# PhotoTriac.net
KiCad netlist of a schematic drawn in EAGLE
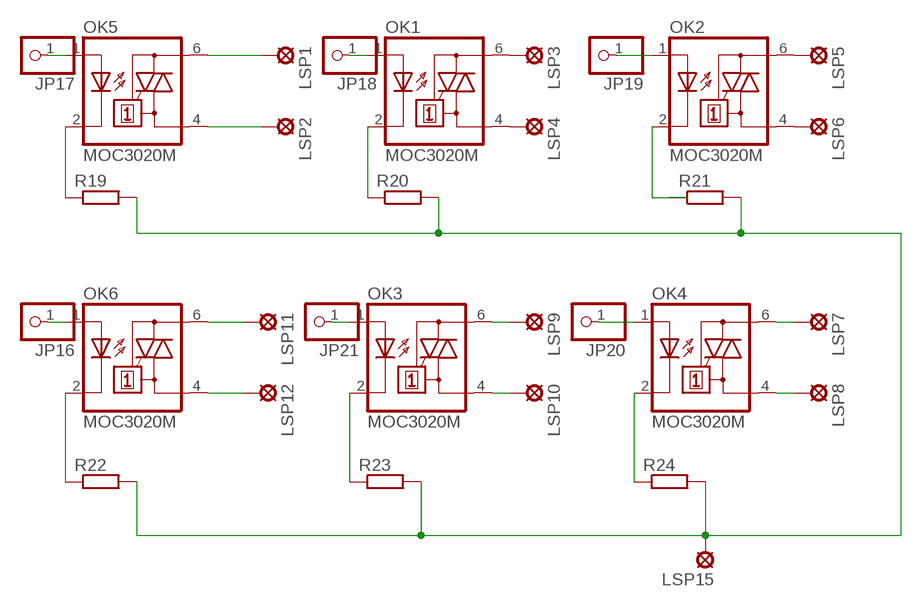
[diagram p0: schematic, sheet 1]

(export (version "E")
  (design (tool "Eeschema 10.0.6"))
  (components
    (comp (ref "JP16")
      (value "PINHD-1X1")
      (footprint "eagle-import:1X01")
      (libsource (lib "eagle-import") (part "PINHD-1X1"))
    )
    (comp (ref "JP17")
      (value "PINHD-1X1")
      (footprint "eagle-import:1X01")
      (libsource (lib "eagle-import") (part "PINHD-1X1"))
    )
    (comp (ref "JP18")
      (value "PINHD-1X1")
      (footprint "eagle-import:1X01")
      (libsource (lib "eagle-import") (part "PINHD-1X1"))
    )
    (comp (ref "JP19")
      (value "PINHD-1X1")
      (footprint "eagle-import:1X01")
      (libsource (lib "eagle-import") (part "PINHD-1X1"))
    )
    (comp (ref "JP20")
      (value "PINHD-1X1")
      (footprint "eagle-import:1X01")
      (libsource (lib "eagle-import") (part "PINHD-1X1"))
    )
    (comp (ref "JP21")
      (value "PINHD-1X1")
      (footprint "eagle-import:1X01")
      (libsource (lib "eagle-import") (part "PINHD-1X1"))
    )
    (comp (ref "LSP1")
      (value "LSP10")
      (footprint "eagle-import:LSP10")
      (libsource (lib "eagle-import") (part "LSP10"))
    )
    (comp (ref "LSP2")
      (value "LSP10")
      (footprint "eagle-import:LSP10")
      (libsource (lib "eagle-import") (part "LSP10"))
    )
    (comp (ref "LSP3")
      (value "LSP10")
      (footprint "eagle-import:LSP10")
      (libsource (lib "eagle-import") (part "LSP10"))
    )
    (comp (ref "LSP4")
      (value "LSP10")
      (footprint "eagle-import:LSP10")
      (libsource (lib "eagle-import") (part "LSP10"))
    )
    (comp (ref "LSP5")
      (value "LSP10")
      (footprint "eagle-import:LSP10")
      (libsource (lib "eagle-import") (part "LSP10"))
    )
    (comp (ref "LSP6")
      (value "LSP10")
      (footprint "eagle-import:LSP10")
      (libsource (lib "eagle-import") (part "LSP10"))
    )
    (comp (ref "LSP7")
      (value "LSP10")
      (footprint "eagle-import:LSP10")
      (libsource (lib "eagle-import") (part "LSP10"))
    )
    (comp (ref "LSP8")
      (value "LSP10")
      (footprint "eagle-import:LSP10")
      (libsource (lib "eagle-import") (part "LSP10"))
    )
    (comp (ref "LSP9")
      (value "LSP10")
      (footprint "eagle-import:LSP10")
      (libsource (lib "eagle-import") (part "LSP10"))
    )
    (comp (ref "LSP10")
      (value "LSP10")
      (footprint "eagle-import:LSP10")
      (libsource (lib "eagle-import") (part "LSP10"))
    )
    (comp (ref "LSP11")
      (value "LSP10")
      (footprint "eagle-import:LSP10")
      (libsource (lib "eagle-import") (part "LSP10"))
    )
    (comp (ref "LSP12")
      (value "LSP10")
      (footprint "eagle-import:LSP10")
      (libsource (lib "eagle-import") (part "LSP10"))
    )
    (comp (ref "LSP15")
      (value "LSP10")
      (footprint "eagle-import:LSP10")
      (libsource (lib "eagle-import") (part "LSP10"))
    )
    (comp (ref "OK1")
      (value "MOC3020M")
      (footprint "eagle-import:DIL06")
      (fields (field (name "MF") "FAIRCHILD SEMICONDUCTOR") (field (name "MPN") "MOC3020-M"))
      (libsource (lib "eagle-import") (part "MOC30M20"))
    )
    (comp (ref "OK2")
      (value "MOC3020M")
      (footprint "eagle-import:DIL06")
      (fields (field (name "MF") "FAIRCHILD SEMICONDUCTOR") (field (name "MPN") "MOC3020-M"))
      (libsource (lib "eagle-import") (part "MOC30M20"))
    )
    (comp (ref "OK3")
      (value "MOC3020M")
      (footprint "eagle-import:DIL06")
      (fields (field (name "MF") "FAIRCHILD SEMICONDUCTOR") (field (name "MPN") "MOC3020-M"))
      (libsource (lib "eagle-import") (part "MOC30M20"))
    )
    (comp (ref "OK4")
      (value "MOC3020M")
      (footprint "eagle-import:DIL06")
      (fields (field (name "MF") "FAIRCHILD SEMICONDUCTOR") (field (name "MPN") "MOC3020-M"))
      (libsource (lib "eagle-import") (part "MOC30M20"))
    )
    (comp (ref "OK5")
      (value "MOC3020M")
      (footprint "eagle-import:DIL06")
      (fields (field (name "MF") "FAIRCHILD SEMICONDUCTOR") (field (name "MPN") "MOC3020-M"))
      (libsource (lib "eagle-import") (part "MOC30M20"))
    )
    (comp (ref "OK6")
      (value "MOC3020M")
      (footprint "eagle-import:DIL06")
      (fields (field (name "MF") "FAIRCHILD SEMICONDUCTOR") (field (name "MPN") "MOC3020-M"))
      (libsource (lib "eagle-import") (part "MOC30M20"))
    )
    (comp (ref "R19")
      (value "R-EU_0207/10")
      (footprint "eagle-import:0207_10")
      (libsource (lib "eagle-import") (part "R-EU_0207/10"))
    )
    (comp (ref "R20")
      (value "R-EU_0207/10")
      (footprint "eagle-import:0207_10")
      (libsource (lib "eagle-import") (part "R-EU_0207/10"))
    )
    (comp (ref "R21")
      (value "R-EU_0207/10")
      (footprint "eagle-import:0207_10")
      (libsource (lib "eagle-import") (part "R-EU_0207/10"))
    )
    (comp (ref "R22")
      (value "R-EU_0207/10")
      (footprint "eagle-import:0207_10")
      (libsource (lib "eagle-import") (part "R-EU_0207/10"))
    )
    (comp (ref "R23")
      (value "R-EU_0207/10")
      (footprint "eagle-import:0207_10")
      (libsource (lib "eagle-import") (part "R-EU_0207/10"))
    )
    (comp (ref "R24")
      (value "R-EU_0207/10")
      (footprint "eagle-import:0207_10")
      (libsource (lib "eagle-import") (part "R-EU_0207/10"))
    )
  )
  (nets
    (net (code "1") (name "Net-(LSP15-PadMP)") (class "Default")
      (node (ref "LSP15") (pin "MP") (pinfunction "MP_MP") (pintype "passive"))
      (node (ref "R19") (pin "2") (pinfunction "2_2") (pintype "passive"))
      (node (ref "R20") (pin "2") (pinfunction "2_2") (pintype "passive"))
      (node (ref "R21") (pin "2") (pinfunction "2_2") (pintype "passive"))
      (node (ref "R22") (pin "2") (pinfunction "2_2") (pintype "passive"))
      (node (ref "R23") (pin "2") (pinfunction "2_2") (pintype "passive"))
      (node (ref "R24") (pin "2") (pinfunction "2_2") (pintype "passive"))
    )
    (net (code "2") (name "Net-(OK1-A)") (class "Default")
      (node (ref "JP18") (pin "1") (pinfunction "1_1") (pintype "passive"))
      (node (ref "OK1") (pin "1") (pinfunction "A_1") (pintype "passive"))
    )
    (net (code "3") (name "Net-(OK1-A1)") (class "Default")
      (node (ref "LSP4") (pin "MP") (pinfunction "MP_MP") (pintype "passive"))
      (node (ref "OK1") (pin "4") (pinfunction "A1_4") (pintype "passive"))
    )
    (net (code "4") (name "Net-(OK1-A2)") (class "Default")
      (node (ref "LSP3") (pin "MP") (pinfunction "MP_MP") (pintype "passive"))
      (node (ref "OK1") (pin "6") (pinfunction "A2_6") (pintype "passive"))
    )
    (net (code "5") (name "Net-(OK1-C)") (class "Default")
      (node (ref "OK1") (pin "2") (pinfunction "C_2") (pintype "passive"))
      (node (ref "R20") (pin "1") (pinfunction "1_1") (pintype "passive"))
    )
    (net (code "6") (name "Net-(OK2-A)") (class "Default")
      (node (ref "JP19") (pin "1") (pinfunction "1_1") (pintype "passive"))
      (node (ref "OK2") (pin "1") (pinfunction "A_1") (pintype "passive"))
    )
    (net (code "7") (name "Net-(OK2-A1)") (class "Default")
      (node (ref "LSP6") (pin "MP") (pinfunction "MP_MP") (pintype "passive"))
      (node (ref "OK2") (pin "4") (pinfunction "A1_4") (pintype "passive"))
    )
    (net (code "8") (name "Net-(OK2-A2)") (class "Default")
      (node (ref "LSP5") (pin "MP") (pinfunction "MP_MP") (pintype "passive"))
      (node (ref "OK2") (pin "6") (pinfunction "A2_6") (pintype "passive"))
    )
    (net (code "9") (name "Net-(OK2-C)") (class "Default")
      (node (ref "OK2") (pin "2") (pinfunction "C_2") (pintype "passive"))
      (node (ref "R21") (pin "1") (pinfunction "1_1") (pintype "passive"))
    )
    (net (code "10") (name "Net-(OK3-A)") (class "Default")
      (node (ref "JP21") (pin "1") (pinfunction "1_1") (pintype "passive"))
      (node (ref "OK3") (pin "1") (pinfunction "A_1") (pintype "passive"))
    )
    (net (code "11") (name "Net-(OK3-A1)") (class "Default")
      (node (ref "LSP10") (pin "MP") (pinfunction "MP_MP") (pintype "passive"))
      (node (ref "OK3") (pin "4") (pinfunction "A1_4") (pintype "passive"))
    )
    (net (code "12") (name "Net-(OK3-A2)") (class "Default")
      (node (ref "LSP9") (pin "MP") (pinfunction "MP_MP") (pintype "passive"))
      (node (ref "OK3") (pin "6") (pinfunction "A2_6") (pintype "passive"))
    )
    (net (code "13") (name "Net-(OK3-C)") (class "Default")
      (node (ref "OK3") (pin "2") (pinfunction "C_2") (pintype "passive"))
      (node (ref "R23") (pin "1") (pinfunction "1_1") (pintype "passive"))
    )
    (net (code "14") (name "Net-(OK4-A)") (class "Default")
      (node (ref "JP20") (pin "1") (pinfunction "1_1") (pintype "passive"))
      (node (ref "OK4") (pin "1") (pinfunction "A_1") (pintype "passive"))
    )
    (net (code "15") (name "Net-(OK4-A1)") (class "Default")
      (node (ref "LSP8") (pin "MP") (pinfunction "MP_MP") (pintype "passive"))
      (node (ref "OK4") (pin "4") (pinfunction "A1_4") (pintype "passive"))
    )
    (net (code "16") (name "Net-(OK4-A2)") (class "Default")
      (node (ref "LSP7") (pin "MP") (pinfunction "MP_MP") (pintype "passive"))
      (node (ref "OK4") (pin "6") (pinfunction "A2_6") (pintype "passive"))
    )
    (net (code "17") (name "Net-(OK4-C)") (class "Default")
      (node (ref "OK4") (pin "2") (pinfunction "C_2") (pintype "passive"))
      (node (ref "R24") (pin "1") (pinfunction "1_1") (pintype "passive"))
    )
    (net (code "18") (name "Net-(OK5-A)") (class "Default")
      (node (ref "JP17") (pin "1") (pinfunction "1_1") (pintype "passive"))
      (node (ref "OK5") (pin "1") (pinfunction "A_1") (pintype "passive"))
    )
    (net (code "19") (name "Net-(OK5-A1)") (class "Default")
      (node (ref "LSP2") (pin "MP") (pinfunction "MP_MP") (pintype "passive"))
      (node (ref "OK5") (pin "4") (pinfunction "A1_4") (pintype "passive"))
    )
    (net (code "20") (name "Net-(OK5-A2)") (class "Default")
      (node (ref "LSP1") (pin "MP") (pinfunction "MP_MP") (pintype "passive"))
      (node (ref "OK5") (pin "6") (pinfunction "A2_6") (pintype "passive"))
    )
    (net (code "21") (name "Net-(OK5-C)") (class "Default")
      (node (ref "OK5") (pin "2") (pinfunction "C_2") (pintype "passive"))
      (node (ref "R19") (pin "1") (pinfunction "1_1") (pintype "passive"))
    )
    (net (code "22") (name "Net-(OK6-A)") (class "Default")
      (node (ref "JP16") (pin "1") (pinfunction "1_1") (pintype "passive"))
      (node (ref "OK6") (pin "1") (pinfunction "A_1") (pintype "passive"))
    )
    (net (code "23") (name "Net-(OK6-A1)") (class "Default")
      (node (ref "LSP12") (pin "MP") (pinfunction "MP_MP") (pintype "passive"))
      (node (ref "OK6") (pin "4") (pinfunction "A1_4") (pintype "passive"))
    )
    (net (code "24") (name "Net-(OK6-A2)") (class "Default")
      (node (ref "LSP11") (pin "MP") (pinfunction "MP_MP") (pintype "passive"))
      (node (ref "OK6") (pin "6") (pinfunction "A2_6") (pintype "passive"))
    )
    (net (code "25") (name "Net-(OK6-C)") (class "Default")
      (node (ref "OK6") (pin "2") (pinfunction "C_2") (pintype "passive"))
      (node (ref "R22") (pin "1") (pinfunction "1_1") (pintype "passive"))
    )
  )
)
